# Breakout.net
KiCad netlist of a schematic drawn in Altium Designer
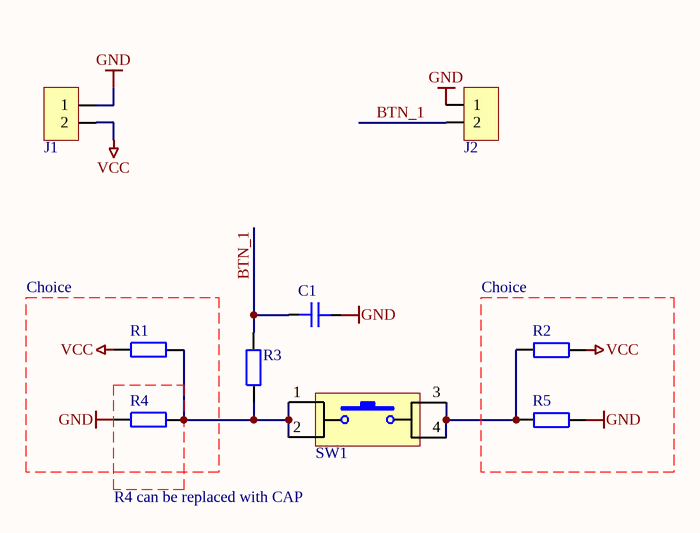
[diagram p0: Breakout.SchDoc]

(export (version "E")
  (design (tool "Eeschema 10.0.6"))
  (components
    (comp (ref "C1")
      (value "? F")
      (footprint "0805C_RF_M")
      (description "Capacitor")
      (fields (field (name "TOLERANCE") "?") (field (name "MANUFACTURER") "Generic Brand"))
      (libsource (lib "AG.Generic") (part "C"))
    )
    (comp (ref "J1")
      (value "PINHDR-2P1")
      (footprint "HEADER-2.54-2P1")
      (description "Pin Header Single Row 2 Positions")
      (libsource (lib "AG.Connectors") (part "PINHDR-2P1"))
    )
    (comp (ref "J2")
      (value "PINHDR-2P1")
      (footprint "HEADER-2.54-2P1")
      (description "Pin Header Single Row 2 Positions")
      (libsource (lib "") (part "PINHDR-2P1_1"))
    )
    (comp (ref "R1")
      (value "? R")
      (footprint "0805R_RF_M")
      (description "Resistor")
      (fields (field (name "TOLERANCE") "?") (field (name "MANUFACTURER") "Generic Brand"))
      (libsource (lib "AG.Generic") (part "R"))
    )
    (comp (ref "R2")
      (value "? R")
      (footprint "0805R_RF_M")
      (description "Resistor")
      (fields (field (name "TOLERANCE") "?") (field (name "MANUFACTURER") "Generic Brand"))
      (libsource (lib "AG.Generic") (part "R"))
    )
    (comp (ref "R3")
      (value "? R")
      (footprint "0805R_RF_M")
      (description "Resistor")
      (fields (field (name "TOLERANCE") "?") (field (name "MANUFACTURER") "Generic Brand"))
      (libsource (lib "AG.Generic") (part "R"))
    )
    (comp (ref "R4")
      (value "? R")
      (footprint "0805R_RF_M")
      (description "Resistor")
      (fields (field (name "TOLERANCE") "?") (field (name "MANUFACTURER") "Generic Brand"))
      (libsource (lib "AG.Generic") (part "R"))
    )
    (comp (ref "R5")
      (value "? R")
      (footprint "0805R_RF_M")
      (description "Resistor")
      (fields (field (name "TOLERANCE") "?") (field (name "MANUFACTURER") "Generic Brand"))
      (libsource (lib "AG.Generic") (part "R"))
    )
    (comp (ref "SW1")
      (value "BTN-SPST-NO-4C")
      (footprint "AG.Electromechanical:TE_CONN_1825910-6-4")
      (description "Tactile Switch SPST-NO")
      (fields (field (name "MANUFACTURER") "Generic Brand"))
      (libsource (lib "AG.Generic") (part "BTN-SPST-NO-4C"))
    )
  )
  (nets
    (net (code "1") (name "/BTN_1") (class "Default")
      (node (ref "C1") (pin "2") (pinfunction "2_2") (pintype "passive"))
      (node (ref "J2") (pin "2") (pinfunction "2_2") (pintype "passive"))
      (node (ref "R3") (pin "2") (pintype "passive"))
    )
    (net (code "2") (name "GND") (class "Default")
      (node (ref "C1") (pin "1") (pinfunction "1_1") (pintype "passive"))
      (node (ref "J1") (pin "1") (pinfunction "1_1") (pintype "passive"))
      (node (ref "J2") (pin "1") (pinfunction "1_1") (pintype "passive"))
      (node (ref "R4") (pin "2") (pintype "passive"))
      (node (ref "R5") (pin "2") (pintype "passive"))
    )
    (net (code "3") (name "Net-(R1-Pad1)") (class "Default")
      (node (ref "R1") (pin "1") (pintype "passive"))
      (node (ref "R3") (pin "1") (pintype "passive"))
      (node (ref "R4") (pin "1") (pintype "passive"))
      (node (ref "SW1") (pin "1") (pinfunction "1_1") (pintype "passive"))
      (node (ref "SW1") (pin "2") (pinfunction "2_2") (pintype "passive"))
    )
    (net (code "4") (name "Net-(R2-Pad1)") (class "Default")
      (node (ref "R2") (pin "1") (pintype "passive"))
      (node (ref "R5") (pin "1") (pintype "passive"))
      (node (ref "SW1") (pin "3") (pinfunction "3_3") (pintype "passive"))
      (node (ref "SW1") (pin "4") (pinfunction "4_4") (pintype "passive"))
    )
    (net (code "5") (name "VCC") (class "Default")
      (node (ref "J1") (pin "2") (pinfunction "2_2") (pintype "passive"))
      (node (ref "R1") (pin "2") (pintype "passive"))
      (node (ref "R2") (pin "2") (pintype "passive"))
    )
  )
)
